# Linx.net
KiCad netlist of a schematic drawn in Altium Designer
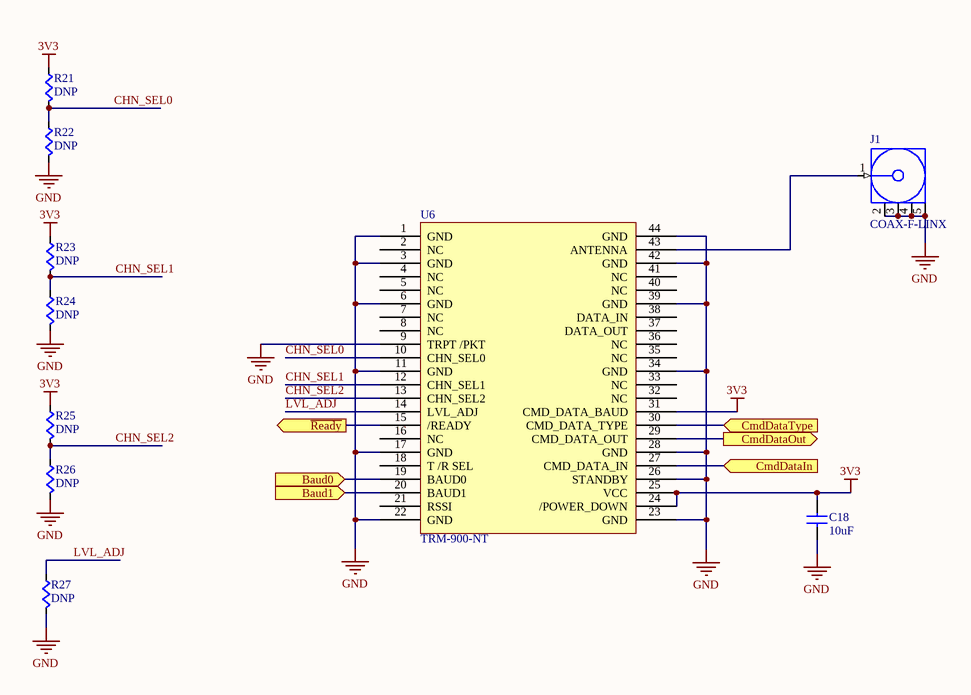
[diagram p0: Linx.SchDoc]

(export (version "E")
  (design (tool "Eeschema 10.0.6"))
  (components
    (comp (ref "C18")
      (value "10uF")
      (footprint "CAPC0603")
      (fields (field (name "Comment") "Cap"))
      (libsource (lib "SubjuGator8") (part "Cap"))
    )
    (comp (ref "J1")
      (value "COAX-F-LINX")
      (footprint "MCX5.08-H5-EDITED")
      (libsource (lib "Connectors") (part "COAX-F-LINX"))
    )
    (comp (ref "R21")
      (value "DNP")
      (footprint "RES0603")
      (fields (field (name "Comment") "Res"))
      (libsource (lib "SubjuGator8") (part "Res"))
    )
    (comp (ref "R22")
      (value "DNP")
      (footprint "RES0603")
      (fields (field (name "Comment") "Res"))
      (libsource (lib "SubjuGator8") (part "Res"))
    )
    (comp (ref "R23")
      (value "DNP")
      (footprint "RES0603")
      (fields (field (name "Comment") "Res"))
      (libsource (lib "SubjuGator8") (part "Res"))
    )
    (comp (ref "R24")
      (value "DNP")
      (footprint "RES0603")
      (fields (field (name "Comment") "Res"))
      (libsource (lib "SubjuGator8") (part "Res"))
    )
    (comp (ref "R25")
      (value "DNP")
      (footprint "RES0603")
      (fields (field (name "Comment") "Res"))
      (libsource (lib "SubjuGator8") (part "Res"))
    )
    (comp (ref "R26")
      (value "DNP")
      (footprint "RES0603")
      (fields (field (name "Comment") "Res"))
      (libsource (lib "SubjuGator8") (part "Res"))
    )
    (comp (ref "R27")
      (value "DNP")
      (footprint "RES0603")
      (fields (field (name "Comment") "Res"))
      (libsource (lib "SubjuGator8") (part "Res"))
    )
    (comp (ref "U6")
      (value "TRM-900-NT")
      (footprint "TRM-900-NT")
      (description "RF TXRX MODULE ISM<1GHZ")
      (libsource (lib "SubjuGator8") (part "TRM-900-NT"))
    )
  )
  (nets
    (net (code "1") (name "/Baud0") (class "Default")
      (node (ref "U6") (pin "19") (pinfunction "BAUD0_19") (pintype "passive"))
    )
    (net (code "2") (name "/Baud1") (class "Default")
      (node (ref "U6") (pin "20") (pinfunction "BAUD1_20") (pintype "passive"))
    )
    (net (code "3") (name "/CHN_SEL0") (class "Default")
      (node (ref "R21") (pin "1") (pinfunction "A_1") (pintype "passive"))
      (node (ref "R22") (pin "2") (pinfunction "B_2") (pintype "passive"))
      (node (ref "U6") (pin "10") (pinfunction "CHN_SEL0_10") (pintype "passive"))
    )
    (net (code "4") (name "/CHN_SEL1") (class "Default")
      (node (ref "R23") (pin "1") (pinfunction "A_1") (pintype "passive"))
      (node (ref "R24") (pin "2") (pinfunction "B_2") (pintype "passive"))
      (node (ref "U6") (pin "12") (pinfunction "CHN_SEL1_12") (pintype "passive"))
    )
    (net (code "5") (name "/CHN_SEL2") (class "Default")
      (node (ref "R25") (pin "1") (pinfunction "A_1") (pintype "passive"))
      (node (ref "R26") (pin "2") (pinfunction "B_2") (pintype "passive"))
      (node (ref "U6") (pin "13") (pinfunction "CHN_SEL2_13") (pintype "passive"))
    )
    (net (code "6") (name "/CmdDataIn") (class "Default")
      (node (ref "U6") (pin "27") (pinfunction "CMD_DATA_IN_27") (pintype "passive"))
    )
    (net (code "7") (name "/CmdDataOut") (class "Default")
      (node (ref "U6") (pin "29") (pinfunction "CMD_DATA_OUT_29") (pintype "passive"))
    )
    (net (code "8") (name "/CmdDataType") (class "Default")
      (node (ref "U6") (pin "30") (pinfunction "CMD_DATA_TYPE_30") (pintype "passive"))
    )
    (net (code "9") (name "/LVL_ADJ") (class "Default")
      (node (ref "R27") (pin "2") (pinfunction "B_2") (pintype "passive"))
      (node (ref "U6") (pin "14") (pinfunction "LVL_ADJ_14") (pintype "passive"))
    )
    (net (code "10") (name "/~{Ready}") (class "Default")
      (node (ref "U6") (pin "15") (pinfunction "/READY_15") (pintype "passive"))
    )
    (net (code "11") (name "3V3") (class "Default")
      (node (ref "C18") (pin "1") (pinfunction "A_1") (pintype "passive"))
      (node (ref "R21") (pin "2") (pinfunction "B_2") (pintype "passive"))
      (node (ref "R23") (pin "2") (pinfunction "B_2") (pintype "passive"))
      (node (ref "R25") (pin "2") (pinfunction "B_2") (pintype "passive"))
      (node (ref "U6") (pin "24") (pinfunction "/POWER_DOWN_24") (pintype "passive"))
      (node (ref "U6") (pin "25") (pinfunction "VCC_25") (pintype "passive"))
      (node (ref "U6") (pin "31") (pinfunction "CMD_DATA_BAUD_31") (pintype "passive"))
    )
    (net (code "12") (name "GND") (class "Default")
      (node (ref "C18") (pin "2") (pinfunction "B_2") (pintype "passive"))
      (node (ref "J1") (pin "2") (pinfunction "GND_2") (pintype "power_in"))
      (node (ref "J1") (pin "3") (pinfunction "GND_3") (pintype "power_in"))
      (node (ref "J1") (pin "4") (pinfunction "GND_4") (pintype "power_in"))
      (node (ref "J1") (pin "5") (pinfunction "GND_5") (pintype "power_in"))
      (node (ref "R22") (pin "1") (pinfunction "A_1") (pintype "passive"))
      (node (ref "R24") (pin "1") (pinfunction "A_1") (pintype "passive"))
      (node (ref "R26") (pin "1") (pinfunction "A_1") (pintype "passive"))
      (node (ref "R27") (pin "1") (pinfunction "A_1") (pintype "passive"))
      (node (ref "U6") (pin "1") (pinfunction "GND_1") (pintype "passive"))
      (node (ref "U6") (pin "11") (pinfunction "GND_11") (pintype "passive"))
      (node (ref "U6") (pin "17") (pinfunction "GND_17") (pintype "passive"))
      (node (ref "U6") (pin "22") (pinfunction "GND_22") (pintype "passive"))
      (node (ref "U6") (pin "23") (pinfunction "GND_23") (pintype "passive"))
      (node (ref "U6") (pin "26") (pinfunction "STANDBY_26") (pintype "passive"))
      (node (ref "U6") (pin "28") (pinfunction "GND_28") (pintype "passive"))
      (node (ref "U6") (pin "3") (pinfunction "GND_3") (pintype "passive"))
      (node (ref "U6") (pin "34") (pinfunction "GND_34") (pintype "passive"))
      (node (ref "U6") (pin "39") (pinfunction "GND_39") (pintype "passive"))
      (node (ref "U6") (pin "42") (pinfunction "GND_42") (pintype "passive"))
      (node (ref "U6") (pin "44") (pinfunction "GND_44") (pintype "passive"))
      (node (ref "U6") (pin "6") (pinfunction "GND_6") (pintype "passive"))
      (node (ref "U6") (pin "9") (pinfunction "TRPT_/PKT_9") (pintype "passive"))
    )
    (net (code "13") (name "Net-(J1-Signal)") (class "Default")
      (node (ref "J1") (pin "1") (pinfunction "Signal_1") (pintype "input"))
      (node (ref "U6") (pin "43") (pinfunction "ANTENNA_43") (pintype "passive"))
    )
    (net (code "14") (name "unconnected-(U6-DATA_IN-Pad38)") (class "Default")
      (node (ref "U6") (pin "38") (pinfunction "DATA_IN_38") (pintype "passive"))
    )
    (net (code "15") (name "unconnected-(U6-DATA_OUT-Pad37)") (class "Default")
      (node (ref "U6") (pin "37") (pinfunction "DATA_OUT_37") (pintype "passive"))
    )
    (net (code "16") (name "unconnected-(U6-NC-Pad2)") (class "Default")
      (node (ref "U6") (pin "2") (pinfunction "NC_2") (pintype "passive"))
    )
    (net (code "17") (name "unconnected-(U6-NC-Pad4)") (class "Default")
      (node (ref "U6") (pin "4") (pinfunction "NC_4") (pintype "passive"))
    )
    (net (code "18") (name "unconnected-(U6-NC-Pad5)") (class "Default")
      (node (ref "U6") (pin "5") (pinfunction "NC_5") (pintype "passive"))
    )
    (net (code "19") (name "unconnected-(U6-NC-Pad7)") (class "Default")
      (node (ref "U6") (pin "7") (pinfunction "NC_7") (pintype "passive"))
    )
    (net (code "20") (name "unconnected-(U6-NC-Pad8)") (class "Default")
      (node (ref "U6") (pin "8") (pinfunction "NC_8") (pintype "passive"))
    )
    (net (code "21") (name "unconnected-(U6-NC-Pad16)") (class "Default")
      (node (ref "U6") (pin "16") (pinfunction "NC_16") (pintype "passive"))
    )
    (net (code "22") (name "unconnected-(U6-NC-Pad32)") (class "Default")
      (node (ref "U6") (pin "32") (pinfunction "NC_32") (pintype "passive"))
    )
    (net (code "23") (name "unconnected-(U6-NC-Pad33)") (class "Default")
      (node (ref "U6") (pin "33") (pinfunction "NC_33") (pintype "passive"))
    )
    (net (code "24") (name "unconnected-(U6-NC-Pad35)") (class "Default")
      (node (ref "U6") (pin "35") (pinfunction "NC_35") (pintype "passive"))
    )
    (net (code "25") (name "unconnected-(U6-NC-Pad36)") (class "Default")
      (node (ref "U6") (pin "36") (pinfunction "NC_36") (pintype "passive"))
    )
    (net (code "26") (name "unconnected-(U6-NC-Pad40)") (class "Default")
      (node (ref "U6") (pin "40") (pinfunction "NC_40") (pintype "passive"))
    )
    (net (code "27") (name "unconnected-(U6-NC-Pad41)") (class "Default")
      (node (ref "U6") (pin "41") (pinfunction "NC_41") (pintype "passive"))
    )
    (net (code "28") (name "unconnected-(U6-RSSI-Pad21)") (class "Default")
      (node (ref "U6") (pin "21") (pinfunction "RSSI_21") (pintype "passive"))
    )
    (net (code "29") (name "unconnected-(U6-T_{slash}R_SEL-Pad18)") (class "Default")
      (node (ref "U6") (pin "18") (pinfunction "T_/R_SEL_18") (pintype "passive"))
    )
  )
)
